# Infineon_Extension_Board.net
KiCad netlist of a schematic drawn in EAGLE
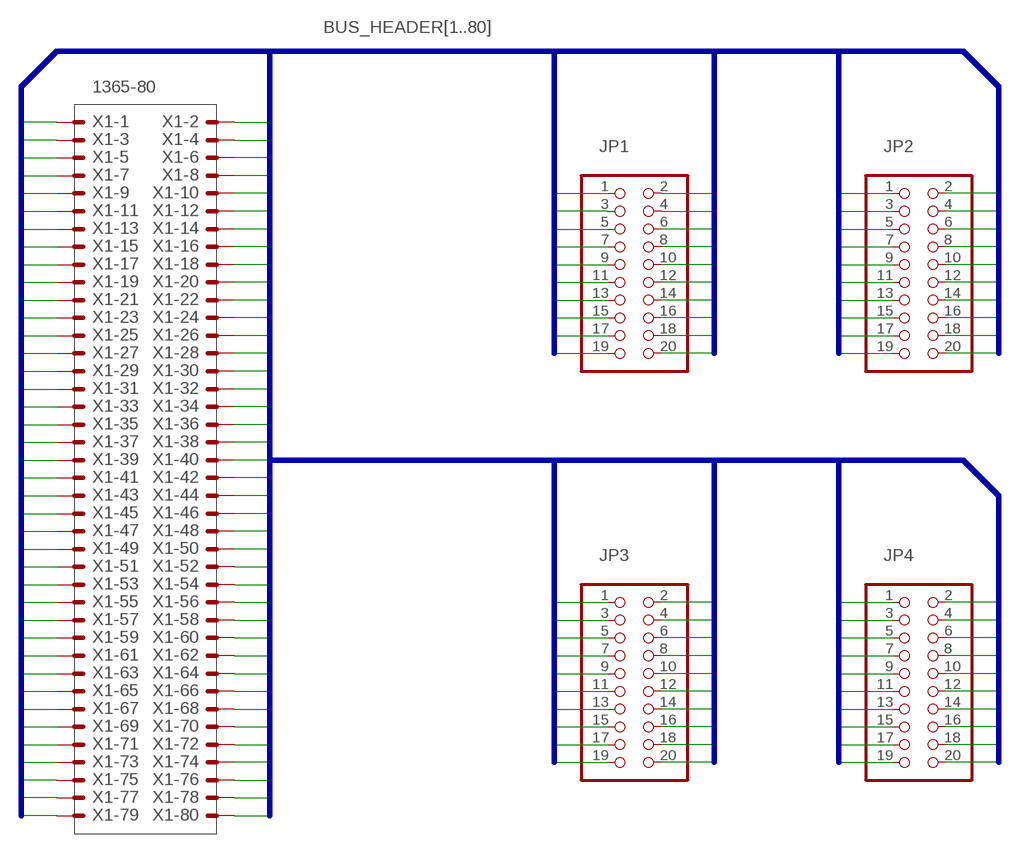
[diagram p0: schematic, sheet 1]

(export (version "E")
  (design (tool "Eeschema 10.0.6"))
  (components
    (comp (ref "JP1")
      (value "PINHD-2X10")
      (footprint "eagle-import:2X10")
      (libsource (lib "eagle-import") (part "PINHD-2X10"))
    )
    (comp (ref "JP2")
      (value "PINHD-2X10")
      (footprint "eagle-import:2X10")
      (libsource (lib "eagle-import") (part "PINHD-2X10"))
    )
    (comp (ref "JP3")
      (value "PINHD-2X10")
      (footprint "eagle-import:2X10")
      (libsource (lib "eagle-import") (part "PINHD-2X10"))
    )
    (comp (ref "JP4")
      (value "PINHD-2X10")
      (footprint "eagle-import:2X10")
      (libsource (lib "eagle-import") (part "PINHD-2X10"))
    )
    (comp (ref "X1")
      (value "1365-80")
      (footprint "eagle-import:1365-80")
      (libsource (lib "eagle-import") (part "1365-80"))
    )
  )
  (nets
    (net (code "1") (name "/BUS_HEADER1") (class "Default")
      (node (ref "JP1") (pin "1") (pinfunction "1_1") (pintype "passive"))
      (node (ref "X1") (pin "1") (pinfunction "S_1") (pintype "passive"))
    )
    (net (code "2") (name "/BUS_HEADER2") (class "Default")
      (node (ref "JP1") (pin "2") (pinfunction "2_2") (pintype "passive"))
      (node (ref "X1") (pin "2") (pinfunction "S_2") (pintype "passive"))
    )
    (net (code "3") (name "/BUS_HEADER3") (class "Default")
      (node (ref "JP1") (pin "3") (pinfunction "3_3") (pintype "passive"))
      (node (ref "X1") (pin "3") (pinfunction "S_3") (pintype "passive"))
    )
    (net (code "4") (name "/BUS_HEADER4") (class "Default")
      (node (ref "JP1") (pin "4") (pinfunction "4_4") (pintype "passive"))
      (node (ref "X1") (pin "4") (pinfunction "S_4") (pintype "passive"))
    )
    (net (code "5") (name "/BUS_HEADER5") (class "Default")
      (node (ref "JP1") (pin "5") (pinfunction "5_5") (pintype "passive"))
      (node (ref "X1") (pin "5") (pinfunction "S_5") (pintype "passive"))
    )
    (net (code "6") (name "/BUS_HEADER6") (class "Default")
      (node (ref "JP1") (pin "6") (pinfunction "6_6") (pintype "passive"))
      (node (ref "X1") (pin "6") (pinfunction "S_6") (pintype "passive"))
    )
    (net (code "7") (name "/BUS_HEADER7") (class "Default")
      (node (ref "JP1") (pin "7") (pinfunction "7_7") (pintype "passive"))
      (node (ref "X1") (pin "7") (pinfunction "S_7") (pintype "passive"))
    )
    (net (code "8") (name "/BUS_HEADER8") (class "Default")
      (node (ref "JP1") (pin "8") (pinfunction "8_8") (pintype "passive"))
      (node (ref "X1") (pin "8") (pinfunction "S_8") (pintype "passive"))
    )
    (net (code "9") (name "/BUS_HEADER9") (class "Default")
      (node (ref "JP1") (pin "9") (pinfunction "9_9") (pintype "passive"))
      (node (ref "X1") (pin "9") (pinfunction "S_9") (pintype "passive"))
    )
    (net (code "10") (name "/BUS_HEADER10") (class "Default")
      (node (ref "JP1") (pin "10") (pinfunction "10_10") (pintype "passive"))
      (node (ref "X1") (pin "10") (pinfunction "S_10") (pintype "passive"))
    )
    (net (code "11") (name "/BUS_HEADER11") (class "Default")
      (node (ref "JP1") (pin "11") (pinfunction "11_11") (pintype "passive"))
      (node (ref "X1") (pin "11") (pinfunction "S_11") (pintype "passive"))
    )
    (net (code "12") (name "/BUS_HEADER12") (class "Default")
      (node (ref "JP1") (pin "12") (pinfunction "12_12") (pintype "passive"))
      (node (ref "X1") (pin "12") (pinfunction "S_12") (pintype "passive"))
    )
    (net (code "13") (name "/BUS_HEADER13") (class "Default")
      (node (ref "JP1") (pin "13") (pinfunction "13_13") (pintype "passive"))
      (node (ref "X1") (pin "13") (pinfunction "S_13") (pintype "passive"))
    )
    (net (code "14") (name "/BUS_HEADER14") (class "Default")
      (node (ref "JP1") (pin "14") (pinfunction "14_14") (pintype "passive"))
      (node (ref "X1") (pin "14") (pinfunction "S_14") (pintype "passive"))
    )
    (net (code "15") (name "/BUS_HEADER15") (class "Default")
      (node (ref "JP1") (pin "15") (pinfunction "15_15") (pintype "passive"))
      (node (ref "X1") (pin "15") (pinfunction "S_15") (pintype "passive"))
    )
    (net (code "16") (name "/BUS_HEADER16") (class "Default")
      (node (ref "JP1") (pin "16") (pinfunction "16_16") (pintype "passive"))
      (node (ref "X1") (pin "16") (pinfunction "S_16") (pintype "passive"))
    )
    (net (code "17") (name "/BUS_HEADER17") (class "Default")
      (node (ref "JP1") (pin "17") (pinfunction "17_17") (pintype "passive"))
      (node (ref "X1") (pin "17") (pinfunction "S_17") (pintype "passive"))
    )
    (net (code "18") (name "/BUS_HEADER18") (class "Default")
      (node (ref "JP1") (pin "18") (pinfunction "18_18") (pintype "passive"))
      (node (ref "X1") (pin "18") (pinfunction "S_18") (pintype "passive"))
    )
    (net (code "19") (name "/BUS_HEADER19") (class "Default")
      (node (ref "JP1") (pin "19") (pinfunction "19_19") (pintype "passive"))
      (node (ref "X1") (pin "19") (pinfunction "S_19") (pintype "passive"))
    )
    (net (code "20") (name "/BUS_HEADER20") (class "Default")
      (node (ref "JP1") (pin "20") (pinfunction "20_20") (pintype "passive"))
      (node (ref "X1") (pin "20") (pinfunction "S_20") (pintype "passive"))
    )
    (net (code "21") (name "/BUS_HEADER21") (class "Default")
      (node (ref "JP2") (pin "1") (pinfunction "1_1") (pintype "passive"))
      (node (ref "X1") (pin "21") (pinfunction "S_21") (pintype "passive"))
    )
    (net (code "22") (name "/BUS_HEADER22") (class "Default")
      (node (ref "JP2") (pin "2") (pinfunction "2_2") (pintype "passive"))
      (node (ref "X1") (pin "22") (pinfunction "S_22") (pintype "passive"))
    )
    (net (code "23") (name "/BUS_HEADER23") (class "Default")
      (node (ref "JP2") (pin "3") (pinfunction "3_3") (pintype "passive"))
      (node (ref "X1") (pin "23") (pinfunction "S_23") (pintype "passive"))
    )
    (net (code "24") (name "/BUS_HEADER24") (class "Default")
      (node (ref "JP2") (pin "4") (pinfunction "4_4") (pintype "passive"))
      (node (ref "X1") (pin "24") (pinfunction "S_24") (pintype "passive"))
    )
    (net (code "25") (name "/BUS_HEADER25") (class "Default")
      (node (ref "JP2") (pin "5") (pinfunction "5_5") (pintype "passive"))
      (node (ref "X1") (pin "25") (pinfunction "S_25") (pintype "passive"))
    )
    (net (code "26") (name "/BUS_HEADER26") (class "Default")
      (node (ref "JP2") (pin "6") (pinfunction "6_6") (pintype "passive"))
      (node (ref "X1") (pin "26") (pinfunction "S_26") (pintype "passive"))
    )
    (net (code "27") (name "/BUS_HEADER27") (class "Default")
      (node (ref "JP2") (pin "7") (pinfunction "7_7") (pintype "passive"))
      (node (ref "X1") (pin "27") (pinfunction "S_27") (pintype "passive"))
    )
    (net (code "28") (name "/BUS_HEADER28") (class "Default")
      (node (ref "JP2") (pin "8") (pinfunction "8_8") (pintype "passive"))
      (node (ref "X1") (pin "28") (pinfunction "S_28") (pintype "passive"))
    )
    (net (code "29") (name "/BUS_HEADER29") (class "Default")
      (node (ref "JP2") (pin "9") (pinfunction "9_9") (pintype "passive"))
      (node (ref "X1") (pin "29") (pinfunction "S_29") (pintype "passive"))
    )
    (net (code "30") (name "/BUS_HEADER30") (class "Default")
      (node (ref "JP2") (pin "10") (pinfunction "10_10") (pintype "passive"))
      (node (ref "X1") (pin "30") (pinfunction "S_30") (pintype "passive"))
    )
    (net (code "31") (name "/BUS_HEADER31") (class "Default")
      (node (ref "JP2") (pin "11") (pinfunction "11_11") (pintype "passive"))
      (node (ref "X1") (pin "31") (pinfunction "S_31") (pintype "passive"))
    )
    (net (code "32") (name "/BUS_HEADER32") (class "Default")
      (node (ref "JP2") (pin "12") (pinfunction "12_12") (pintype "passive"))
      (node (ref "X1") (pin "32") (pinfunction "S_32") (pintype "passive"))
    )
    (net (code "33") (name "/BUS_HEADER33") (class "Default")
      (node (ref "JP2") (pin "13") (pinfunction "13_13") (pintype "passive"))
      (node (ref "X1") (pin "33") (pinfunction "S_33") (pintype "passive"))
    )
    (net (code "34") (name "/BUS_HEADER34") (class "Default")
      (node (ref "JP2") (pin "14") (pinfunction "14_14") (pintype "passive"))
      (node (ref "X1") (pin "34") (pinfunction "S_34") (pintype "passive"))
    )
    (net (code "35") (name "/BUS_HEADER35") (class "Default")
      (node (ref "JP2") (pin "15") (pinfunction "15_15") (pintype "passive"))
      (node (ref "X1") (pin "35") (pinfunction "S_35") (pintype "passive"))
    )
    (net (code "36") (name "/BUS_HEADER36") (class "Default")
      (node (ref "JP2") (pin "16") (pinfunction "16_16") (pintype "passive"))
      (node (ref "X1") (pin "36") (pinfunction "S_36") (pintype "passive"))
    )
    (net (code "37") (name "/BUS_HEADER37") (class "Default")
      (node (ref "JP2") (pin "17") (pinfunction "17_17") (pintype "passive"))
      (node (ref "X1") (pin "37") (pinfunction "S_37") (pintype "passive"))
    )
    (net (code "38") (name "/BUS_HEADER38") (class "Default")
      (node (ref "JP2") (pin "18") (pinfunction "18_18") (pintype "passive"))
      (node (ref "X1") (pin "38") (pinfunction "S_38") (pintype "passive"))
    )
    (net (code "39") (name "/BUS_HEADER39") (class "Default")
      (node (ref "JP2") (pin "19") (pinfunction "19_19") (pintype "passive"))
      (node (ref "X1") (pin "39") (pinfunction "S_39") (pintype "passive"))
    )
    (net (code "40") (name "/BUS_HEADER40") (class "Default")
      (node (ref "JP2") (pin "20") (pinfunction "20_20") (pintype "passive"))
      (node (ref "X1") (pin "40") (pinfunction "S_40") (pintype "passive"))
    )
    (net (code "41") (name "/BUS_HEADER41") (class "Default")
      (node (ref "JP3") (pin "1") (pinfunction "1_1") (pintype "passive"))
      (node (ref "X1") (pin "41") (pinfunction "S_41") (pintype "passive"))
    )
    (net (code "42") (name "/BUS_HEADER42") (class "Default")
      (node (ref "JP3") (pin "2") (pinfunction "2_2") (pintype "passive"))
      (node (ref "X1") (pin "42") (pinfunction "S_42") (pintype "passive"))
    )
    (net (code "43") (name "/BUS_HEADER43") (class "Default")
      (node (ref "JP3") (pin "3") (pinfunction "3_3") (pintype "passive"))
      (node (ref "X1") (pin "43") (pinfunction "S_43") (pintype "passive"))
    )
    (net (code "44") (name "/BUS_HEADER44") (class "Default")
      (node (ref "JP3") (pin "4") (pinfunction "4_4") (pintype "passive"))
      (node (ref "X1") (pin "44") (pinfunction "S_44") (pintype "passive"))
    )
    (net (code "45") (name "/BUS_HEADER45") (class "Default")
      (node (ref "JP3") (pin "5") (pinfunction "5_5") (pintype "passive"))
      (node (ref "X1") (pin "45") (pinfunction "S_45") (pintype "passive"))
    )
    (net (code "46") (name "/BUS_HEADER46") (class "Default")
      (node (ref "JP3") (pin "6") (pinfunction "6_6") (pintype "passive"))
      (node (ref "X1") (pin "46") (pinfunction "S_46") (pintype "passive"))
    )
    (net (code "47") (name "/BUS_HEADER47") (class "Default")
      (node (ref "JP3") (pin "7") (pinfunction "7_7") (pintype "passive"))
      (node (ref "X1") (pin "47") (pinfunction "S_47") (pintype "passive"))
    )
    (net (code "48") (name "/BUS_HEADER48") (class "Default")
      (node (ref "JP3") (pin "8") (pinfunction "8_8") (pintype "passive"))
      (node (ref "X1") (pin "48") (pinfunction "S_48") (pintype "passive"))
    )
    (net (code "49") (name "/BUS_HEADER49") (class "Default")
      (node (ref "JP3") (pin "9") (pinfunction "9_9") (pintype "passive"))
      (node (ref "X1") (pin "49") (pinfunction "S_49") (pintype "passive"))
    )
    (net (code "50") (name "/BUS_HEADER50") (class "Default")
      (node (ref "JP3") (pin "10") (pinfunction "10_10") (pintype "passive"))
      (node (ref "X1") (pin "50") (pinfunction "S_50") (pintype "passive"))
    )
    (net (code "51") (name "/BUS_HEADER51") (class "Default")
      (node (ref "JP3") (pin "11") (pinfunction "11_11") (pintype "passive"))
      (node (ref "X1") (pin "51") (pinfunction "S_51") (pintype "passive"))
    )
    (net (code "52") (name "/BUS_HEADER52") (class "Default")
      (node (ref "JP3") (pin "12") (pinfunction "12_12") (pintype "passive"))
      (node (ref "X1") (pin "52") (pinfunction "S_52") (pintype "passive"))
    )
    (net (code "53") (name "/BUS_HEADER53") (class "Default")
      (node (ref "JP3") (pin "13") (pinfunction "13_13") (pintype "passive"))
      (node (ref "X1") (pin "53") (pinfunction "S_53") (pintype "passive"))
    )
    (net (code "54") (name "/BUS_HEADER54") (class "Default")
      (node (ref "JP3") (pin "14") (pinfunction "14_14") (pintype "passive"))
      (node (ref "X1") (pin "54") (pinfunction "S_54") (pintype "passive"))
    )
    (net (code "55") (name "/BUS_HEADER55") (class "Default")
      (node (ref "JP3") (pin "15") (pinfunction "15_15") (pintype "passive"))
      (node (ref "X1") (pin "55") (pinfunction "S_55") (pintype "passive"))
    )
    (net (code "56") (name "/BUS_HEADER56") (class "Default")
      (node (ref "JP3") (pin "16") (pinfunction "16_16") (pintype "passive"))
      (node (ref "X1") (pin "56") (pinfunction "S_56") (pintype "passive"))
    )
    (net (code "57") (name "/BUS_HEADER57") (class "Default")
      (node (ref "JP3") (pin "17") (pinfunction "17_17") (pintype "passive"))
      (node (ref "X1") (pin "57") (pinfunction "S_57") (pintype "passive"))
    )
    (net (code "58") (name "/BUS_HEADER58") (class "Default")
      (node (ref "JP3") (pin "18") (pinfunction "18_18") (pintype "passive"))
      (node (ref "X1") (pin "58") (pinfunction "S_58") (pintype "passive"))
    )
    (net (code "59") (name "/BUS_HEADER59") (class "Default")
      (node (ref "JP3") (pin "19") (pinfunction "19_19") (pintype "passive"))
      (node (ref "X1") (pin "59") (pinfunction "S_59") (pintype "passive"))
    )
    (net (code "60") (name "/BUS_HEADER60") (class "Default")
      (node (ref "JP3") (pin "20") (pinfunction "20_20") (pintype "passive"))
      (node (ref "X1") (pin "60") (pinfunction "S_60") (pintype "passive"))
    )
    (net (code "61") (name "/BUS_HEADER61") (class "Default")
      (node (ref "JP4") (pin "1") (pinfunction "1_1") (pintype "passive"))
      (node (ref "X1") (pin "61") (pinfunction "S_61") (pintype "passive"))
    )
    (net (code "62") (name "/BUS_HEADER62") (class "Default")
      (node (ref "JP4") (pin "2") (pinfunction "2_2") (pintype "passive"))
      (node (ref "X1") (pin "62") (pinfunction "S_62") (pintype "passive"))
    )
    (net (code "63") (name "/BUS_HEADER63") (class "Default")
      (node (ref "JP4") (pin "3") (pinfunction "3_3") (pintype "passive"))
      (node (ref "X1") (pin "63") (pinfunction "S_63") (pintype "passive"))
    )
    (net (code "64") (name "/BUS_HEADER64") (class "Default")
      (node (ref "JP4") (pin "4") (pinfunction "4_4") (pintype "passive"))
      (node (ref "X1") (pin "64") (pinfunction "S_64") (pintype "passive"))
    )
    (net (code "65") (name "/BUS_HEADER65") (class "Default")
      (node (ref "JP4") (pin "5") (pinfunction "5_5") (pintype "passive"))
      (node (ref "X1") (pin "65") (pinfunction "S_65") (pintype "passive"))
    )
    (net (code "66") (name "/BUS_HEADER66") (class "Default")
      (node (ref "JP4") (pin "6") (pinfunction "6_6") (pintype "passive"))
      (node (ref "X1") (pin "66") (pinfunction "S_66") (pintype "passive"))
    )
    (net (code "67") (name "/BUS_HEADER67") (class "Default")
      (node (ref "JP4") (pin "7") (pinfunction "7_7") (pintype "passive"))
      (node (ref "X1") (pin "67") (pinfunction "S_67") (pintype "passive"))
    )
    (net (code "68") (name "/BUS_HEADER68") (class "Default")
      (node (ref "JP4") (pin "8") (pinfunction "8_8") (pintype "passive"))
      (node (ref "X1") (pin "68") (pinfunction "S_68") (pintype "passive"))
    )
    (net (code "69") (name "/BUS_HEADER69") (class "Default")
      (node (ref "JP4") (pin "9") (pinfunction "9_9") (pintype "passive"))
      (node (ref "X1") (pin "69") (pinfunction "S_69") (pintype "passive"))
    )
    (net (code "70") (name "/BUS_HEADER70") (class "Default")
      (node (ref "JP4") (pin "10") (pinfunction "10_10") (pintype "passive"))
      (node (ref "X1") (pin "70") (pinfunction "S_70") (pintype "passive"))
    )
    (net (code "71") (name "/BUS_HEADER71") (class "Default")
      (node (ref "JP4") (pin "11") (pinfunction "11_11") (pintype "passive"))
      (node (ref "X1") (pin "71") (pinfunction "S_71") (pintype "passive"))
    )
    (net (code "72") (name "/BUS_HEADER72") (class "Default")
      (node (ref "JP4") (pin "12") (pinfunction "12_12") (pintype "passive"))
      (node (ref "X1") (pin "72") (pinfunction "S_72") (pintype "passive"))
    )
    (net (code "73") (name "/BUS_HEADER73") (class "Default")
      (node (ref "JP4") (pin "13") (pinfunction "13_13") (pintype "passive"))
      (node (ref "X1") (pin "73") (pinfunction "S_73") (pintype "passive"))
    )
    (net (code "74") (name "/BUS_HEADER74") (class "Default")
      (node (ref "JP4") (pin "14") (pinfunction "14_14") (pintype "passive"))
      (node (ref "X1") (pin "74") (pinfunction "S_74") (pintype "passive"))
    )
    (net (code "75") (name "/BUS_HEADER75") (class "Default")
      (node (ref "JP4") (pin "15") (pinfunction "15_15") (pintype "passive"))
      (node (ref "X1") (pin "75") (pinfunction "S_75") (pintype "passive"))
    )
    (net (code "76") (name "/BUS_HEADER76") (class "Default")
      (node (ref "JP4") (pin "16") (pinfunction "16_16") (pintype "passive"))
      (node (ref "X1") (pin "76") (pinfunction "S_76") (pintype "passive"))
    )
    (net (code "77") (name "/BUS_HEADER77") (class "Default")
      (node (ref "JP4") (pin "17") (pinfunction "17_17") (pintype "passive"))
      (node (ref "X1") (pin "77") (pinfunction "S_77") (pintype "passive"))
    )
    (net (code "78") (name "/BUS_HEADER78") (class "Default")
      (node (ref "JP4") (pin "18") (pinfunction "18_18") (pintype "passive"))
      (node (ref "X1") (pin "78") (pinfunction "S_78") (pintype "passive"))
    )
    (net (code "79") (name "/BUS_HEADER79") (class "Default")
      (node (ref "JP4") (pin "19") (pinfunction "19_19") (pintype "passive"))
      (node (ref "X1") (pin "79") (pinfunction "S_79") (pintype "passive"))
    )
    (net (code "80") (name "/BUS_HEADER80") (class "Default")
      (node (ref "JP4") (pin "20") (pinfunction "20_20") (pintype "passive"))
      (node (ref "X1") (pin "80") (pinfunction "S_80") (pintype "passive"))
    )
  )
)
